# PWR_PMIC.net
KiCad netlist of a schematic drawn in Altium Designer
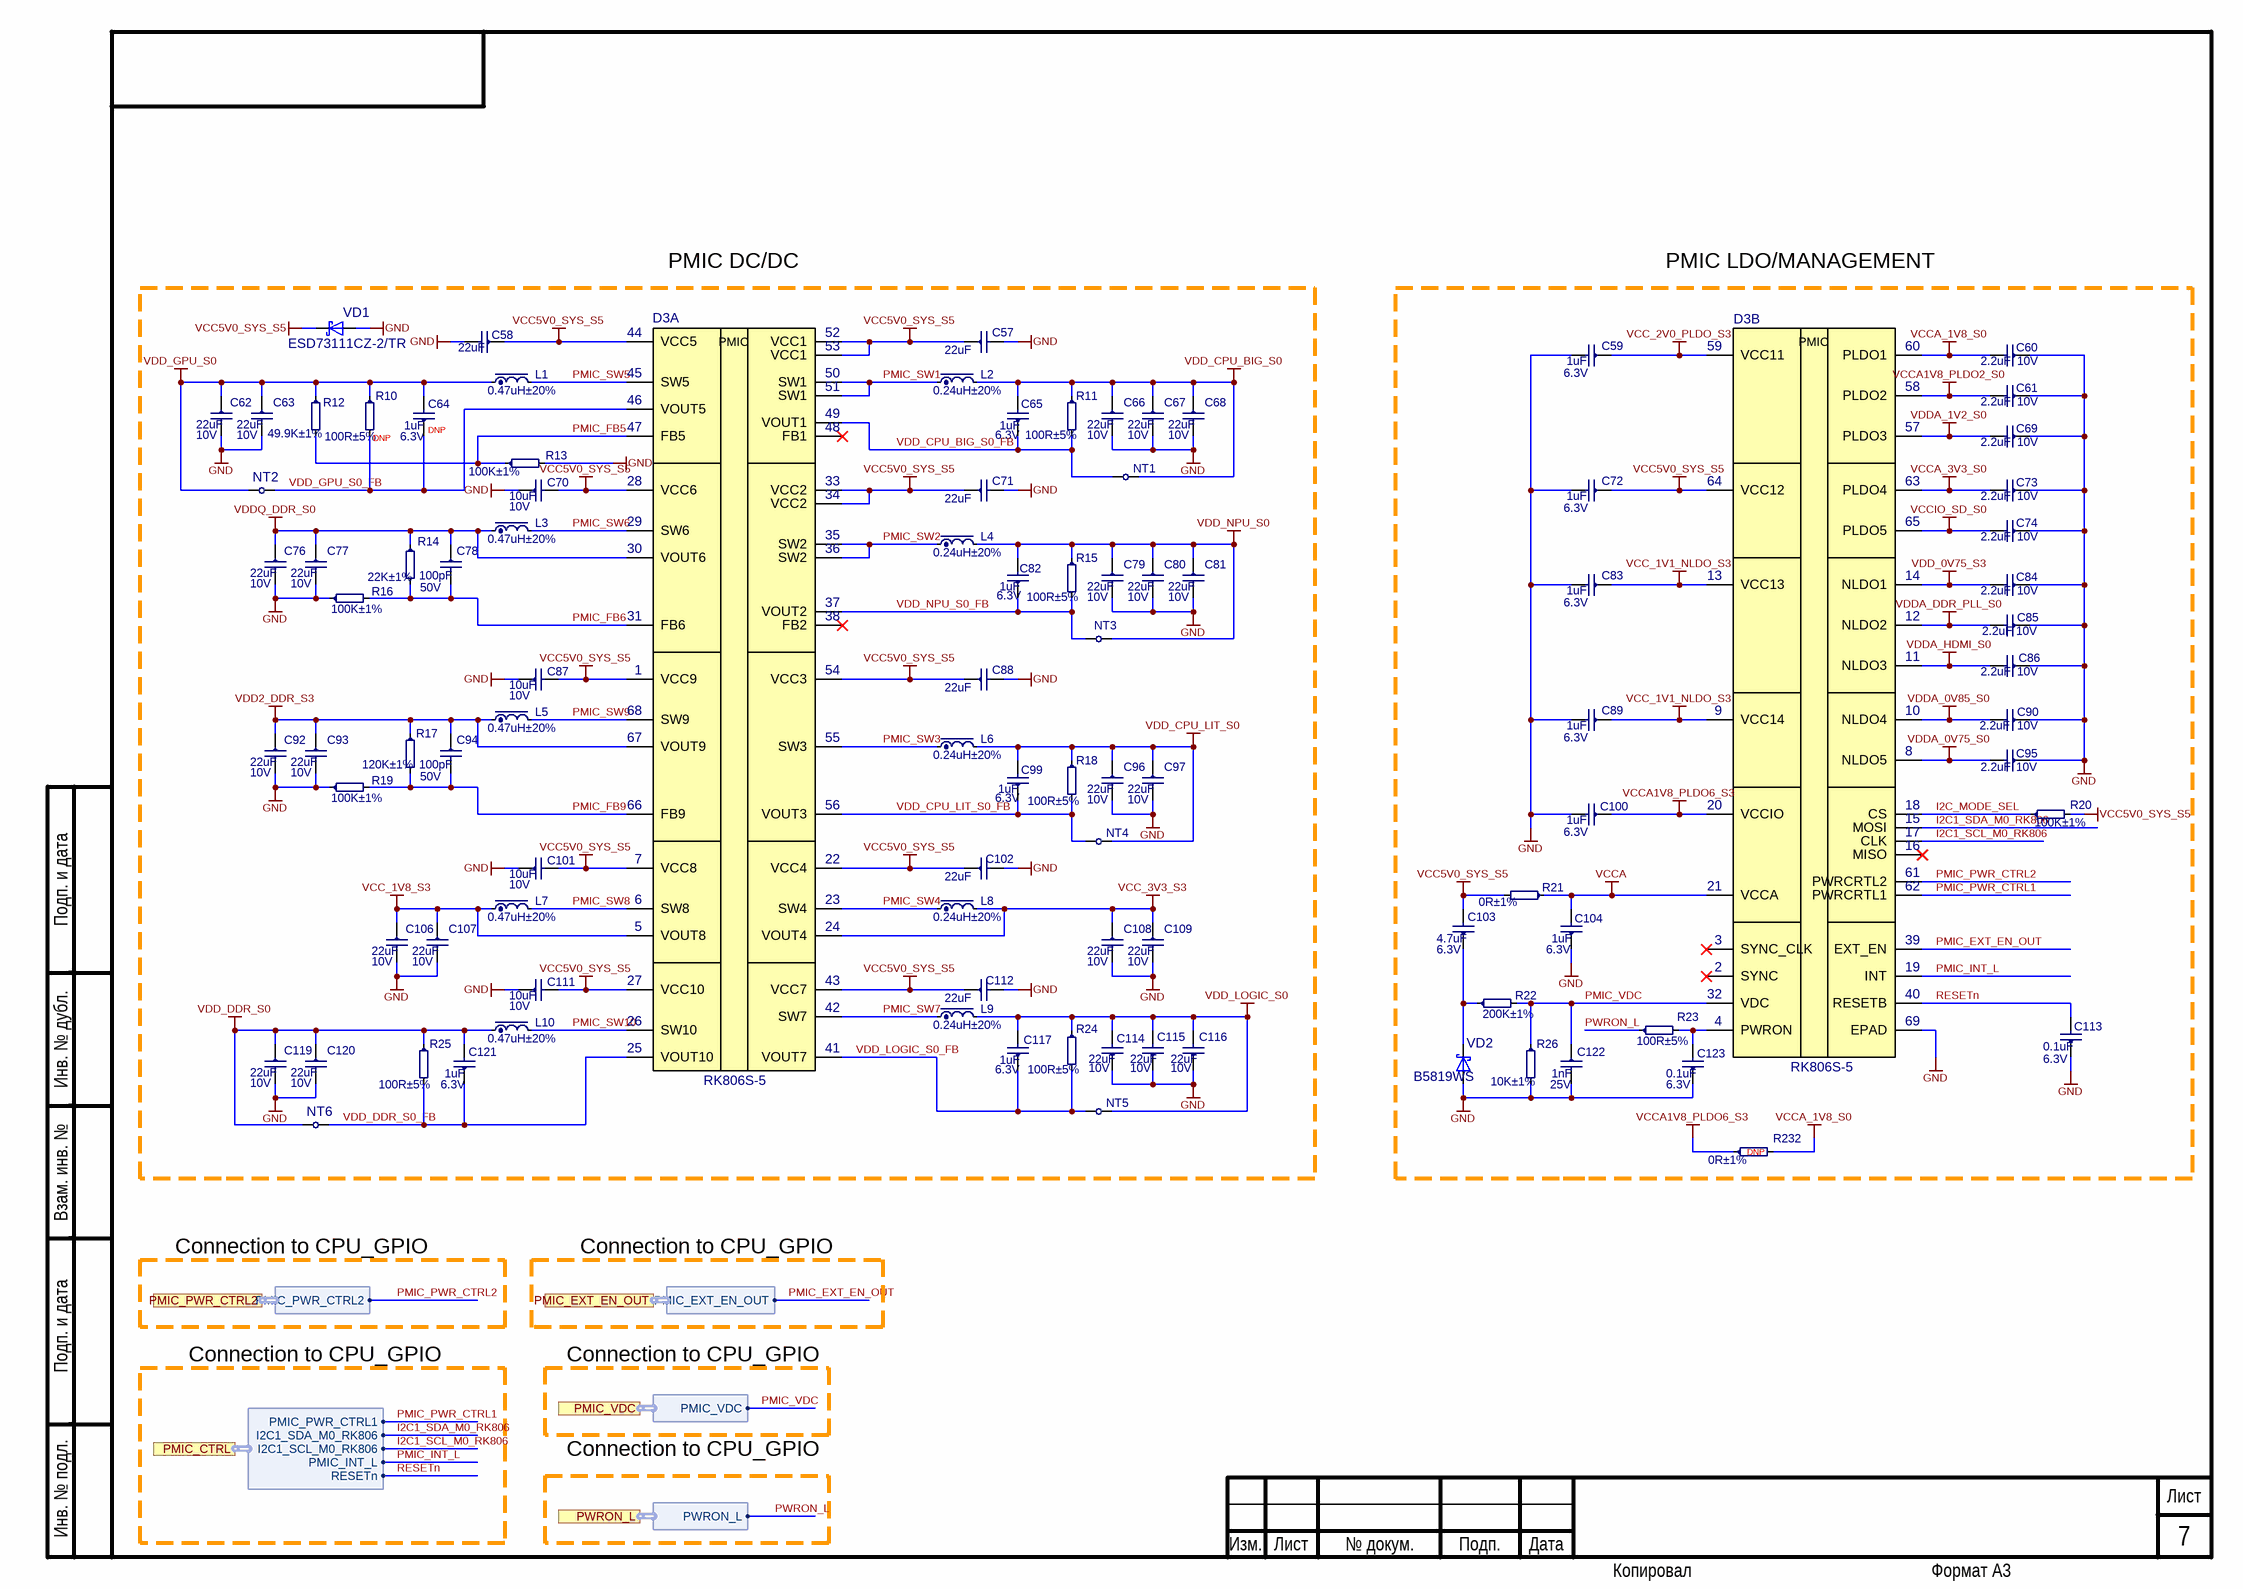
[diagram p0: PWR_PMIC.SchDoc]

(export (version "E")
  (design (tool "Eeschema 10.0.6"))
  (components
    (comp (ref "C57")
      (value "22uF")
      (footprint "C0603")
      (fields
        (field (name "VOLTAGE") "10V")
        (field (name "PART NUMBER") "0603-X5R-10V-22uF±20%")
        (field (name "TOLERANCE") "20%")
      )
      (libsource (lib "ATB") (part "C"))
    )
    (comp (ref "C58")
      (value "22uF")
      (footprint "C0603")
      (fields
        (field (name "VOLTAGE") "10V")
        (field (name "PART NUMBER") "0603-X5R-10V-22uF±20%")
        (field (name "TOLERANCE") "20%")
      )
      (libsource (lib "ATB") (part "C"))
    )
    (comp (ref "C59")
      (value "1uF")
      (footprint "C0201")
      (fields
        (field (name "VOLTAGE") "6.3V")
        (field (name "PART NUMBER") "0201-X5R-6.3V-1uF±20%")
        (field (name "TOLERANCE") "20%")
        (field (name "MANUFACTURER") "Murata Electronics")
      )
      (libsource (lib "ATB") (part "C"))
    )
    (comp (ref "C60")
      (value "2.2uF")
      (footprint "C0402")
      (fields
        (field (name "VOLTAGE") "10V")
        (field (name "PART NUMBER") "0402-X5R-10V-2.2uF±10%")
        (field (name "TOLERANCE") "10%")
        (field (name "MANUFACTURER") "Yageo")
      )
      (libsource (lib "ATB") (part "C"))
    )
    (comp (ref "C61")
      (value "2.2uF")
      (footprint "C0402")
      (fields
        (field (name "VOLTAGE") "10V")
        (field (name "PART NUMBER") "0402-X5R-10V-2.2uF±10%")
        (field (name "TOLERANCE") "10%")
        (field (name "MANUFACTURER") "Yageo")
      )
      (libsource (lib "ATB") (part "C"))
    )
    (comp (ref "C62")
      (value "22uF")
      (footprint "C0603")
      (fields
        (field (name "VOLTAGE") "10V")
        (field (name "PART NUMBER") "0603-X5R-10V-22uF±20%")
        (field (name "TOLERANCE") "20%")
        (field (name "MANUFACTURER") "Samsung Electro-Mechanics")
      )
      (libsource (lib "ATB") (part "C"))
    )
    (comp (ref "C63")
      (value "22uF")
      (footprint "C0603")
      (fields
        (field (name "VOLTAGE") "10V")
        (field (name "PART NUMBER") "0603-X5R-10V-22uF±20%")
        (field (name "TOLERANCE") "20%")
        (field (name "MANUFACTURER") "Samsung Electro-Mechanics")
      )
      (libsource (lib "ATB") (part "C"))
    )
    (comp (ref "C64")
      (value "1uF")
      (footprint "C0201")
      (fields
        (field (name "VOLTAGE") "6.3V")
        (field (name "PART NUMBER") "0201-X5R-6.3V-1uF±20%")
        (field (name "TOLERANCE") "20%")
        (field (name "MANUFACTURER") "Murata Electronics")
      )
      (libsource (lib "ATB") (part "C"))
    )
    (comp (ref "C65")
      (value "1uF")
      (footprint "C0201")
      (fields
        (field (name "VOLTAGE") "6.3V")
        (field (name "PART NUMBER") "0201-X5R-6.3V-1uF±20%")
        (field (name "TOLERANCE") "20%")
        (field (name "MANUFACTURER") "Murata Electronics")
      )
      (libsource (lib "ATB") (part "C"))
    )
    (comp (ref "C66")
      (value "22uF")
      (footprint "C0603")
      (fields
        (field (name "VOLTAGE") "10V")
        (field (name "PART NUMBER") "0603-X5R-10V-22uF±20%")
        (field (name "TOLERANCE") "20%")
        (field (name "MANUFACTURER") "Samsung Electro-Mechanics")
      )
      (libsource (lib "ATB") (part "C"))
    )
    (comp (ref "C67")
      (value "22uF")
      (footprint "C0603")
      (fields
        (field (name "VOLTAGE") "10V")
        (field (name "PART NUMBER") "0603-X5R-10V-22uF±20%")
        (field (name "TOLERANCE") "20%")
        (field (name "MANUFACTURER") "Samsung Electro-Mechanics")
      )
      (libsource (lib "ATB") (part "C"))
    )
    (comp (ref "C68")
      (value "22uF")
      (footprint "C0603")
      (fields
        (field (name "VOLTAGE") "10V")
        (field (name "PART NUMBER") "0603-X5R-10V-22uF±20%")
        (field (name "TOLERANCE") "20%")
        (field (name "MANUFACTURER") "Samsung Electro-Mechanics")
      )
      (libsource (lib "ATB") (part "C"))
    )
    (comp (ref "C69")
      (value "2.2uF")
      (footprint "C0402")
      (fields
        (field (name "VOLTAGE") "10V")
        (field (name "PART NUMBER") "0402-X5R-10V-2.2uF±10%")
        (field (name "TOLERANCE") "10%")
        (field (name "MANUFACTURER") "Yageo")
      )
      (libsource (lib "ATB") (part "C"))
    )
    (comp (ref "C70")
      (value "10uF")
      (footprint "C0603")
      (fields
        (field (name "VOLTAGE") "10V")
        (field (name "PART NUMBER") "0603-X5R-10V-10uF±10%")
        (field (name "TOLERANCE") "10%")
        (field (name "MANUFACTURER") "Yageo")
      )
      (libsource (lib "ATB") (part "C"))
    )
    (comp (ref "C71")
      (value "22uF")
      (footprint "C0603")
      (fields
        (field (name "VOLTAGE") "10V")
        (field (name "PART NUMBER") "0603-X5R-10V-22uF±20%")
        (field (name "TOLERANCE") "20%")
      )
      (libsource (lib "ATB") (part "C"))
    )
    (comp (ref "C72")
      (value "1uF")
      (footprint "C0201")
      (fields
        (field (name "VOLTAGE") "6.3V")
        (field (name "PART NUMBER") "0201-X5R-6.3V-1uF±20%")
        (field (name "TOLERANCE") "20%")
        (field (name "MANUFACTURER") "Murata Electronics")
      )
      (libsource (lib "ATB") (part "C"))
    )
    (comp (ref "C73")
      (value "2.2uF")
      (footprint "C0402")
      (fields
        (field (name "VOLTAGE") "10V")
        (field (name "PART NUMBER") "0402-X5R-10V-2.2uF±10%")
        (field (name "TOLERANCE") "10%")
        (field (name "MANUFACTURER") "Yageo")
      )
      (libsource (lib "ATB") (part "C"))
    )
    (comp (ref "C74")
      (value "2.2uF")
      (footprint "C0402")
      (fields
        (field (name "VOLTAGE") "10V")
        (field (name "PART NUMBER") "0402-X5R-10V-2.2uF±10%")
        (field (name "TOLERANCE") "10%")
        (field (name "MANUFACTURER") "Yageo")
      )
      (libsource (lib "ATB") (part "C"))
    )
    (comp (ref "C76")
      (value "22uF")
      (footprint "C0603")
      (fields
        (field (name "VOLTAGE") "10V")
        (field (name "PART NUMBER") "0603-X5R-10V-22uF±20%")
        (field (name "TOLERANCE") "20%")
        (field (name "MANUFACTURER") "Samsung Electro-Mechanics")
      )
      (libsource (lib "ATB") (part "C"))
    )
    (comp (ref "C77")
      (value "22uF")
      (footprint "C0603")
      (fields
        (field (name "VOLTAGE") "10V")
        (field (name "PART NUMBER") "0603-X5R-10V-22uF±20%")
        (field (name "TOLERANCE") "20%")
        (field (name "MANUFACTURER") "Samsung Electro-Mechanics")
      )
      (libsource (lib "ATB") (part "C"))
    )
    (comp (ref "C78")
      (value "100pF")
      (footprint "C0402")
      (fields
        (field (name "VOLTAGE") "50V")
        (field (name "PART NUMBER") "0402-NP0-50V-100pF±1%")
        (field (name "TOLERANCE") "1%")
        (field (name "MANUFACTURER") "Yageo")
      )
      (libsource (lib "ATB") (part "C"))
    )
    (comp (ref "C79")
      (value "22uF")
      (footprint "C0603")
      (fields
        (field (name "VOLTAGE") "10V")
        (field (name "PART NUMBER") "0603-X5R-10V-22uF±20%")
        (field (name "TOLERANCE") "20%")
        (field (name "MANUFACTURER") "Samsung Electro-Mechanics")
      )
      (libsource (lib "ATB") (part "C"))
    )
    (comp (ref "C80")
      (value "22uF")
      (footprint "C0603")
      (fields
        (field (name "VOLTAGE") "10V")
        (field (name "PART NUMBER") "0603-X5R-10V-22uF±20%")
        (field (name "TOLERANCE") "20%")
        (field (name "MANUFACTURER") "Samsung Electro-Mechanics")
      )
      (libsource (lib "ATB") (part "C"))
    )
    (comp (ref "C81")
      (value "22uF")
      (footprint "C0603")
      (fields
        (field (name "VOLTAGE") "10V")
        (field (name "PART NUMBER") "0603-X5R-10V-22uF±20%")
        (field (name "TOLERANCE") "20%")
        (field (name "MANUFACTURER") "Samsung Electro-Mechanics")
      )
      (libsource (lib "ATB") (part "C"))
    )
    (comp (ref "C82")
      (value "1uF")
      (footprint "C0201")
      (fields
        (field (name "VOLTAGE") "6.3V")
        (field (name "PART NUMBER") "0201-X5R-6.3V-1uF±20%")
        (field (name "TOLERANCE") "20%")
        (field (name "MANUFACTURER") "Murata Electronics")
      )
      (libsource (lib "ATB") (part "C"))
    )
    (comp (ref "C83")
      (value "1uF")
      (footprint "C0201")
      (fields
        (field (name "VOLTAGE") "6.3V")
        (field (name "PART NUMBER") "0201-X5R-6.3V-1uF±20%")
        (field (name "TOLERANCE") "20%")
        (field (name "MANUFACTURER") "Murata Electronics")
      )
      (libsource (lib "ATB") (part "C"))
    )
    (comp (ref "C84")
      (value "2.2uF")
      (footprint "C0402")
      (fields
        (field (name "VOLTAGE") "10V")
        (field (name "PART NUMBER") "0402-X5R-10V-2.2uF±10%")
        (field (name "TOLERANCE") "10%")
        (field (name "MANUFACTURER") "Yageo")
      )
      (libsource (lib "ATB") (part "C"))
    )
    (comp (ref "C85")
      (value "2.2uF")
      (footprint "C0402")
      (fields
        (field (name "VOLTAGE") "10V")
        (field (name "PART NUMBER") "0402-X5R-10V-2.2uF±10%")
        (field (name "TOLERANCE") "10%")
        (field (name "MANUFACTURER") "Yageo")
      )
      (libsource (lib "ATB") (part "C"))
    )
    (comp (ref "C86")
      (value "2.2uF")
      (footprint "C0402")
      (fields
        (field (name "VOLTAGE") "10V")
        (field (name "PART NUMBER") "0402-X5R-10V-2.2uF±10%")
        (field (name "TOLERANCE") "10%")
        (field (name "MANUFACTURER") "Yageo")
      )
      (libsource (lib "ATB") (part "C"))
    )
    (comp (ref "C87")
      (value "10uF")
      (footprint "C0603")
      (fields
        (field (name "VOLTAGE") "10V")
        (field (name "PART NUMBER") "0603-X5R-10V-10uF±10%")
        (field (name "TOLERANCE") "10%")
        (field (name "MANUFACTURER") "Yageo")
      )
      (libsource (lib "ATB") (part "C"))
    )
    (comp (ref "C88")
      (value "22uF")
      (footprint "C0603")
      (fields
        (field (name "VOLTAGE") "10V")
        (field (name "PART NUMBER") "0603-X5R-10V-22uF±20%")
        (field (name "TOLERANCE") "20%")
      )
      (libsource (lib "ATB") (part "C"))
    )
    (comp (ref "C89")
      (value "1uF")
      (footprint "C0201")
      (fields
        (field (name "VOLTAGE") "6.3V")
        (field (name "PART NUMBER") "0201-X5R-6.3V-1uF±20%")
        (field (name "TOLERANCE") "20%")
        (field (name "MANUFACTURER") "Murata Electronics")
      )
      (libsource (lib "ATB") (part "C"))
    )
    (comp (ref "C90")
      (value "2.2uF")
      (footprint "C0402")
      (fields
        (field (name "VOLTAGE") "10V")
        (field (name "PART NUMBER") "0402-X5R-10V-2.2uF±10%")
        (field (name "TOLERANCE") "10%")
        (field (name "MANUFACTURER") "Yageo")
      )
      (libsource (lib "ATB") (part "C"))
    )
    (comp (ref "C92")
      (value "22uF")
      (footprint "C0603")
      (fields
        (field (name "VOLTAGE") "10V")
        (field (name "PART NUMBER") "0603-X5R-10V-22uF±20%")
        (field (name "TOLERANCE") "20%")
        (field (name "MANUFACTURER") "Samsung Electro-Mechanics")
      )
      (libsource (lib "ATB") (part "C"))
    )
    (comp (ref "C93")
      (value "22uF")
      (footprint "C0603")
      (fields
        (field (name "VOLTAGE") "10V")
        (field (name "PART NUMBER") "0603-X5R-10V-22uF±20%")
        (field (name "TOLERANCE") "20%")
        (field (name "MANUFACTURER") "Samsung Electro-Mechanics")
      )
      (libsource (lib "ATB") (part "C"))
    )
    (comp (ref "C94")
      (value "100pF")
      (footprint "C0402")
      (fields
        (field (name "VOLTAGE") "50V")
        (field (name "PART NUMBER") "0402-NP0-50V-100pF±1%")
        (field (name "TOLERANCE") "1%")
        (field (name "MANUFACTURER") "Yageo")
      )
      (libsource (lib "ATB") (part "C"))
    )
    (comp (ref "C95")
      (value "2.2uF")
      (footprint "C0402")
      (fields
        (field (name "VOLTAGE") "10V")
        (field (name "PART NUMBER") "0402-X5R-10V-2.2uF±10%")
        (field (name "TOLERANCE") "10%")
        (field (name "MANUFACTURER") "Yageo")
      )
      (libsource (lib "ATB") (part "C"))
    )
    (comp (ref "C96")
      (value "22uF")
      (footprint "C0603")
      (fields
        (field (name "VOLTAGE") "10V")
        (field (name "PART NUMBER") "0603-X5R-10V-22uF±20%")
        (field (name "TOLERANCE") "20%")
        (field (name "MANUFACTURER") "Samsung Electro-Mechanics")
      )
      (libsource (lib "ATB") (part "C"))
    )
    (comp (ref "C97")
      (value "22uF")
      (footprint "C0603")
      (fields
        (field (name "VOLTAGE") "10V")
        (field (name "PART NUMBER") "0603-X5R-10V-22uF±20%")
        (field (name "TOLERANCE") "20%")
        (field (name "MANUFACTURER") "Samsung Electro-Mechanics")
      )
      (libsource (lib "ATB") (part "C"))
    )
    (comp (ref "C99")
      (value "1uF")
      (footprint "C0201")
      (fields
        (field (name "VOLTAGE") "6.3V")
        (field (name "PART NUMBER") "0201-X5R-6.3V-1uF±20%")
        (field (name "TOLERANCE") "20%")
        (field (name "MANUFACTURER") "Murata Electronics")
      )
      (libsource (lib "ATB") (part "C"))
    )
    (comp (ref "C100")
      (value "1uF")
      (footprint "C0201")
      (fields
        (field (name "VOLTAGE") "6.3V")
        (field (name "PART NUMBER") "0201-X5R-6.3V-1uF±20%")
        (field (name "TOLERANCE") "20%")
        (field (name "MANUFACTURER") "Murata Electronics")
      )
      (libsource (lib "ATB") (part "C"))
    )
    (comp (ref "C101")
      (value "10uF")
      (footprint "C0603")
      (fields
        (field (name "VOLTAGE") "10V")
        (field (name "PART NUMBER") "0603-X5R-10V-10uF±10%")
        (field (name "TOLERANCE") "10%")
        (field (name "MANUFACTURER") "Yageo")
      )
      (libsource (lib "ATB") (part "C"))
    )
    (comp (ref "C102")
      (value "22uF")
      (footprint "C0603")
      (fields
        (field (name "VOLTAGE") "10V")
        (field (name "PART NUMBER") "0603-X5R-10V-22uF±20%")
        (field (name "TOLERANCE") "20%")
      )
      (libsource (lib "ATB") (part "C"))
    )
    (comp (ref "C103")
      (value "4.7uF")
      (footprint "C0201")
      (fields
        (field (name "VOLTAGE") "6.3V")
        (field (name "PART NUMBER") "0201-X5R-6.3V-4.7uF±20%")
        (field (name "TOLERANCE") "20%")
        (field (name "MANUFACTURER") "Murata Electronics")
      )
      (libsource (lib "ATB") (part "C"))
    )
    (comp (ref "C104")
      (value "1uF")
      (footprint "C0201")
      (fields
        (field (name "VOLTAGE") "6.3V")
        (field (name "PART NUMBER") "0201-X5R-6.3V-1uF±20%")
        (field (name "TOLERANCE") "20%")
        (field (name "MANUFACTURER") "Murata Electronics")
      )
      (libsource (lib "ATB") (part "C"))
    )
    (comp (ref "C106")
      (value "22uF")
      (footprint "C0603")
      (fields
        (field (name "VOLTAGE") "10V")
        (field (name "PART NUMBER") "0603-X5R-10V-22uF±20%")
        (field (name "TOLERANCE") "20%")
        (field (name "MANUFACTURER") "Samsung Electro-Mechanics")
      )
      (libsource (lib "ATB") (part "C"))
    )
    (comp (ref "C107")
      (value "22uF")
      (footprint "C0603")
      (fields
        (field (name "VOLTAGE") "10V")
        (field (name "PART NUMBER") "0603-X5R-10V-22uF±20%")
        (field (name "TOLERANCE") "20%")
        (field (name "MANUFACTURER") "Samsung Electro-Mechanics")
      )
      (libsource (lib "ATB") (part "C"))
    )
    (comp (ref "C108")
      (value "22uF")
      (footprint "C0603")
      (fields
        (field (name "VOLTAGE") "10V")
        (field (name "PART NUMBER") "0603-X5R-10V-22uF±20%")
        (field (name "TOLERANCE") "20%")
        (field (name "MANUFACTURER") "Samsung Electro-Mechanics")
      )
      (libsource (lib "ATB") (part "C"))
    )
    (comp (ref "C109")
      (value "22uF")
      (footprint "C0603")
      (fields
        (field (name "VOLTAGE") "10V")
        (field (name "PART NUMBER") "0603-X5R-10V-22uF±20%")
        (field (name "TOLERANCE") "20%")
        (field (name "MANUFACTURER") "Samsung Electro-Mechanics")
      )
      (libsource (lib "ATB") (part "C"))
    )
    (comp (ref "C111")
      (value "10uF")
      (footprint "C0603")
      (fields
        (field (name "VOLTAGE") "10V")
        (field (name "PART NUMBER") "0603-X5R-10V-10uF±10%")
        (field (name "TOLERANCE") "10%")
        (field (name "MANUFACTURER") "Yageo")
      )
      (libsource (lib "ATB") (part "C"))
    )
    (comp (ref "C112")
      (value "22uF")
      (footprint "C0603")
      (fields
        (field (name "VOLTAGE") "10V")
        (field (name "PART NUMBER") "0603-X5R-10V-22uF±20%")
        (field (name "TOLERANCE") "20%")
      )
      (libsource (lib "ATB") (part "C"))
    )
    (comp (ref "C113")
      (value "0.1uF")
      (footprint "C0201")
      (fields
        (field (name "VOLTAGE") "6.3V")
        (field (name "PART NUMBER") "0201-X5R-6.3V-0.1uF±10%")
        (field (name "TOLERANCE") "10%")
        (field (name "MANUFACTURER") "Yageo")
      )
      (libsource (lib "ATB") (part "C"))
    )
    (comp (ref "C114")
      (value "22uF")
      (footprint "C0603")
      (fields
        (field (name "VOLTAGE") "10V")
        (field (name "PART NUMBER") "0603-X5R-10V-22uF±20%")
        (field (name "TOLERANCE") "20%")
        (field (name "MANUFACTURER") "Samsung Electro-Mechanics")
      )
      (libsource (lib "ATB") (part "C"))
    )
    (comp (ref "C115")
      (value "22uF")
      (footprint "C0603")
      (fields
        (field (name "VOLTAGE") "10V")
        (field (name "PART NUMBER") "0603-X5R-10V-22uF±20%")
        (field (name "TOLERANCE") "20%")
        (field (name "MANUFACTURER") "Samsung Electro-Mechanics")
      )
      (libsource (lib "ATB") (part "C"))
    )
    (comp (ref "C116")
      (value "22uF")
      (footprint "C0603")
      (fields
        (field (name "VOLTAGE") "10V")
        (field (name "PART NUMBER") "0603-X5R-10V-22uF±20%")
        (field (name "TOLERANCE") "20%")
        (field (name "MANUFACTURER") "Samsung Electro-Mechanics")
      )
      (libsource (lib "ATB") (part "C"))
    )
    (comp (ref "C117")
      (value "1uF")
      (footprint "C0201")
      (fields
        (field (name "VOLTAGE") "6.3V")
        (field (name "PART NUMBER") "0201-X5R-6.3V-1uF±20%")
        (field (name "TOLERANCE") "20%")
        (field (name "MANUFACTURER") "Murata Electronics")
      )
      (libsource (lib "ATB") (part "C"))
    )
    (comp (ref "C119")
      (value "22uF")
      (footprint "C0603")
      (fields
        (field (name "VOLTAGE") "10V")
        (field (name "PART NUMBER") "0603-X5R-10V-22uF±20%")
        (field (name "TOLERANCE") "20%")
        (field (name "MANUFACTURER") "Samsung Electro-Mechanics")
      )
      (libsource (lib "ATB") (part "C"))
    )
    (comp (ref "C120")
      (value "22uF")
      (footprint "C0603")
      (fields
        (field (name "VOLTAGE") "10V")
        (field (name "PART NUMBER") "0603-X5R-10V-22uF±20%")
        (field (name "TOLERANCE") "20%")
        (field (name "MANUFACTURER") "Samsung Electro-Mechanics")
      )
      (libsource (lib "ATB") (part "C"))
    )
    (comp (ref "C121")
      (value "1uF")
      (footprint "C0201")
      (fields
        (field (name "VOLTAGE") "6.3V")
        (field (name "PART NUMBER") "0201-X5R-6.3V-1uF±20%")
        (field (name "TOLERANCE") "20%")
        (field (name "MANUFACTURER") "Murata Electronics")
      )
      (libsource (lib "ATB") (part "C"))
    )
    (comp (ref "C122")
      (value "1nF")
      (footprint "C0201")
      (fields
        (field (name "VOLTAGE") "25V")
        (field (name "PART NUMBER") "0201-C0G-25V-1nF±5%")
        (field (name "TOLERANCE") "5%")
        (field (name "MANUFACTURER") "muRata")
      )
      (libsource (lib "ATB") (part "C"))
    )
    (comp (ref "C123")
      (value "0.1uF")
      (footprint "C0201")
      (fields
        (field (name "VOLTAGE") "6.3V")
        (field (name "PART NUMBER") "0201-X5R-6.3V-0.1uF±10%")
        (field (name "TOLERANCE") "10%")
        (field (name "MANUFACTURER") "Yageo")
      )
      (libsource (lib "ATB") (part "C"))
    )
    (comp (ref "D3")
      (value "RK806S-5")
      (footprint "RK806-1")
      (description "Power Management")
      (fields (field (name "MANUFACTURER") "Rockchip"))
      (libsource (lib "LIB_RK") (part "RK806S-5"))
    )
    (comp (ref "L1")
      (value "0.47uH±20%")
      (footprint "L0806")
      (fields
        (field (name "PART NUMBER") "0806-5A-0.47uH±20%")
        (field (name "TOLERANCE") "20%")
        (field (name "MANUFACTURER") "INPAQ")
      )
      (libsource (lib "ATB") (part "L"))
    )
    (comp (ref "L2")
      (value "0.24uH±20%")
      (footprint "L0806")
      (fields
        (field (name "PART NUMBER") "0806-4.4A-0.24uH±20%")
        (field (name "TOLERANCE") "20%")
        (field (name "MANUFACTURER") "cjiang")
      )
      (libsource (lib "ATB") (part "L"))
    )
    (comp (ref "L3")
      (value "0.47uH±20%")
      (footprint "L0806")
      (fields
        (field (name "PART NUMBER") "0806-5A-0.47uH±20%")
        (field (name "TOLERANCE") "20%")
        (field (name "MANUFACTURER") "INPAQ")
      )
      (libsource (lib "ATB") (part "L"))
    )
    (comp (ref "L4")
      (value "0.24uH±20%")
      (footprint "L0806")
      (fields
        (field (name "PART NUMBER") "0806-4.4A-0.24uH±20%")
        (field (name "TOLERANCE") "20%")
        (field (name "MANUFACTURER") "cjiang")
      )
      (libsource (lib "ATB") (part "L"))
    )
    (comp (ref "L5")
      (value "0.47uH±20%")
      (footprint "L0806")
      (fields
        (field (name "PART NUMBER") "0806-5A-0.47uH±20%")
        (field (name "TOLERANCE") "20%")
        (field (name "MANUFACTURER") "INPAQ")
      )
      (libsource (lib "ATB") (part "L"))
    )
    (comp (ref "L6")
      (value "0.24uH±20%")
      (footprint "L0806")
      (fields
        (field (name "PART NUMBER") "0806-4.4A-0.24uH±20%")
        (field (name "TOLERANCE") "20%")
        (field (name "MANUFACTURER") "cjiang")
      )
      (libsource (lib "ATB") (part "L"))
    )
    (comp (ref "L7")
      (value "0.47uH±20%")
      (footprint "L0806")
      (fields
        (field (name "PART NUMBER") "0806-5A-0.47uH±20%")
        (field (name "TOLERANCE") "20%")
        (field (name "MANUFACTURER") "INPAQ")
      )
      (libsource (lib "ATB") (part "L"))
    )
    (comp (ref "L8")
      (value "0.24uH±20%")
      (footprint "L0806")
      (fields
        (field (name "PART NUMBER") "0806-4.4A-0.24uH±20%")
        (field (name "TOLERANCE") "20%")
        (field (name "MANUFACTURER") "cjiang")
      )
      (libsource (lib "ATB") (part "L"))
    )
    (comp (ref "L9")
      (value "0.24uH±20%")
      (footprint "L0806")
      (fields
        (field (name "PART NUMBER") "0806-4.4A-0.24uH±20%")
        (field (name "TOLERANCE") "20%")
        (field (name "MANUFACTURER") "cjiang")
      )
      (libsource (lib "ATB") (part "L"))
    )
    (comp (ref "L10")
      (value "0.47uH±20%")
      (footprint "L0806")
      (fields
        (field (name "PART NUMBER") "0806-5A-0.47uH±20%")
        (field (name "TOLERANCE") "20%")
        (field (name "MANUFACTURER") "INPAQ")
      )
      (libsource (lib "ATB") (part "L"))
    )
    (comp (ref "NT1")
      (value "~")
      (footprint "NetTie_0.6mm_close")
      (fields (field (name "PART NUMBER") "Перемычка закрытая_0.6мм"))
      (libsource (lib "ATB") (part "NetTie"))
    )
    (comp (ref "NT2")
      (value "~")
      (footprint "NetTie_0.6mm_close")
      (fields (field (name "PART NUMBER") "Перемычка закрытая_0.6мм"))
      (libsource (lib "ATB") (part "NetTie"))
    )
    (comp (ref "NT3")
      (value "~")
      (footprint "NetTie_0.6mm_close")
      (fields (field (name "PART NUMBER") "Перемычка закрытая_0.6мм"))
      (libsource (lib "ATB") (part "NetTie"))
    )
    (comp (ref "NT4")
      (value "~")
      (footprint "NetTie_0.6mm_close")
      (fields (field (name "PART NUMBER") "Перемычка закрытая_0.6мм"))
      (libsource (lib "ATB") (part "NetTie"))
    )
    (comp (ref "NT5")
      (value "~")
      (footprint "NetTie_0.6mm_close")
      (fields (field (name "PART NUMBER") "Перемычка закрытая_0.6мм"))
      (libsource (lib "ATB") (part "NetTie"))
    )
    (comp (ref "NT6")
      (value "~")
      (footprint "NetTie_0.6mm_close")
      (fields (field (name "PART NUMBER") "Перемычка закрытая_0.6мм"))
      (libsource (lib "ATB") (part "NetTie"))
    )
    (comp (ref "R10")
      (value "100R±5%")
      (footprint "R0201")
      (fields
        (field (name "PART NUMBER") "0201-0.05W-100R-200ppm-5%")
        (field (name "TOLERANCE") "5%")
        (field (name "MANUFACTURER") "Yageo")
      )
      (libsource (lib "ATB") (part "R"))
    )
    (comp (ref "R11")
      (value "100R±5%")
      (footprint "R0201")
      (fields
        (field (name "PART NUMBER") "0201-0.05W-100R-200ppm-5%")
        (field (name "TOLERANCE") "5%")
        (field (name "MANUFACTURER") "Yageo")
      )
      (libsource (lib "ATB") (part "R"))
    )
    (comp (ref "R12")
      (value "49.9K±1%")
      (footprint "R0402")
      (description "Chip Resistor 0402 49.9kΩ ±1% 50V ±100ppm/℃ Thick Film")
      (fields (field (name "PART NUMBER") "0402-0.0625W-49.9K-100ppm±1%") (field (name "TOLERANCE") "1%"))
      (libsource (lib "ATB") (part "R"))
    )
    (comp (ref "R13")
      (value "100K±1%")
      (footprint "R0402")
      (description "Chip Resistor 0402 100kΩ ±1% 50V ±100ppm/℃ Thick Film")
      (fields (field (name "PART NUMBER") "0402-0.0625W-100K-100ppm±1%") (field (name "TOLERANCE") "1%"))
      (libsource (lib "ATB") (part "R"))
    )
    (comp (ref "R14")
      (value "22K±1%")
      (footprint "R0402")
      (fields
        (field (name "PART NUMBER") "0402-0.0625W-22K-100ppm±1%")
        (field (name "TOLERANCE") "1%")
        (field (name "MANUFACTURER") "Yageo")
      )
      (libsource (lib "ATB") (part "R"))
    )
    (comp (ref "R15")
      (value "100R±5%")
      (footprint "R0201")
      (fields
        (field (name "PART NUMBER") "0201-0.05W-100R-200ppm-5%")
        (field (name "TOLERANCE") "5%")
        (field (name "MANUFACTURER") "Yageo")
      )
      (libsource (lib "ATB") (part "R"))
    )
    (comp (ref "R16")
      (value "100K±1%")
      (footprint "R0402")
      (description "Chip Resistor 0402 100kΩ ±1% 50V ±100ppm/℃ Thick Film")
      (fields (field (name "PART NUMBER") "0402-0.0625W-100K-100ppm±1%") (field (name "TOLERANCE") "1%"))
      (libsource (lib "ATB") (part "R"))
    )
    (comp (ref "R17")
      (value "120K±1%")
      (footprint "R0402")
      (fields
        (field (name "PART NUMBER") "0402-0.0625W-120K-100ppm±1%")
        (field (name "TOLERANCE") "1%")
        (field (name "MANUFACTURER") "Yageo")
      )
      (libsource (lib "ATB") (part "R"))
    )
    (comp (ref "R18")
      (value "100R±5%")
      (footprint "R0201")
      (fields
        (field (name "PART NUMBER") "0201-0.05W-100R-200ppm-5%")
        (field (name "TOLERANCE") "5%")
        (field (name "MANUFACTURER") "Yageo")
      )
      (libsource (lib "ATB") (part "R"))
    )
    (comp (ref "R19")
      (value "100K±1%")
      (footprint "R0402")
      (description "Chip Resistor 0402 100kΩ ±1% 50V ±100ppm/℃ Thick Film")
      (fields (field (name "PART NUMBER") "0402-0.0625W-100K-100ppm±1%") (field (name "TOLERANCE") "1%"))
      (libsource (lib "ATB") (part "R"))
    )
    (comp (ref "R20")
      (value "100K±1%")
      (footprint "R0201")
      (fields
        (field (name "PART NUMBER") "0201-0.05W-100K-5%")
        (field (name "TOLERANCE") "1%")
        (field (name "MANUFACTURER") "Yageo")
      )
      (libsource (lib "ATB") (part "R"))
    )
    (comp (ref "R21")
      (value "0R±1%")
      (footprint "R0402")
      (description "Chip Resistor 0402 0Ω ±1% 50V ±100ppm/℃ Thick Film")
      (fields (field (name "PART NUMBER") "0402-0.0625W-0R-100ppm±1%") (field (name "TOLERANCE") "1%"))
      (libsource (lib "ATB") (part "R"))
    )
    (comp (ref "R22")
      (value "200K±1%")
      (footprint "R0201")
      (fields
        (field (name "PART NUMBER") "0201-0.05W-200K-100ppm-1%")
        (field (name "TOLERANCE") "1%")
        (field (name "MANUFACTURER") "Yageo")
      )
      (libsource (lib "ATB") (part "R"))
    )
    (comp (ref "R23")
      (value "100R±5%")
      (footprint "R0201")
      (fields
        (field (name "PART NUMBER") "0201-0.05W-100R-200ppm-5%")
        (field (name "TOLERANCE") "5%")
        (field (name "MANUFACTURER") "Yageo")
      )
      (libsource (lib "ATB") (part "R"))
    )
    (comp (ref "R24")
      (value "100R±5%")
      (footprint "R0201")
      (fields
        (field (name "PART NUMBER") "0201-0.05W-100R-200ppm-5%")
        (field (name "TOLERANCE") "5%")
        (field (name "MANUFACTURER") "Yageo")
      )
      (libsource (lib "ATB") (part "R"))
    )
    (comp (ref "R25")
      (value "100R±5%")
      (footprint "R0201")
      (fields
        (field (name "PART NUMBER") "0201-0.05W-100R-200ppm-5%")
        (field (name "TOLERANCE") "5%")
        (field (name "MANUFACTURER") "Yageo")
      )
      (libsource (lib "ATB") (part "R"))
    )
    (comp (ref "R26")
      (value "10K±1%")
      (footprint "R0201")
      (fields
        (field (name "PART NUMBER") "0201-0.05W-10K-100ppm-1%")
        (field (name "TOLERANCE") "1%")
        (field (name "MANUFACTURER") "Yageo")
      )
      (libsource (lib "ATB") (part "R"))
    )
    (comp (ref "R232")
      (value "0R±1%")
      (footprint "R0402")
      (description "Chip Resistor 0402 0Ω ±1% 50V ±100ppm/℃ Thick Film")
      (fields (field (name "PART NUMBER") "0402-0.0625W-0R-100ppm±1%") (field (name "TOLERANCE") "1%"))
      (libsource (lib "ATB") (part "R"))
    )
    (comp (ref "VD1")
      (value "ESD73111CZ-2/TR")
      (footprint "ESD73111CZ-2/TR")
      (description "6.5VC Clamp 6A@8/20us Ipp ESD DIODE DWN0603-2L")
      (fields (field (name "MANUFACTURER") "WILLSEMI"))
      (libsource (lib "LIB_RK") (part "ESD73111CZ-2/TR"))
    )
    (comp (ref "VD2")
      (value "B5819WS")
      (footprint "B5819WS")
      (description "Rectifier Diode, Schottky, 1 Phase, 1 Element, 1A, 40V V(RRM), Silicon")
      (libsource (lib "LIB_RK") (part "B5819WS"))
    )
  )
  (nets
    (net (code "2") (name "/I2C1_SCL_M0_RK806") (class "Default")
      (node (ref "D3") (pin "17") (pinfunction "CLK_17") (pintype "passive"))
    )
    (net (code "3") (name "/I2C1_SDA_M0_RK806") (class "Default")
      (node (ref "D3") (pin "15") (pinfunction "MOSI_15") (pintype "passive"))
    )
    (net (code "4") (name "/I2C_MODE_SEL") (class "Default")
      (node (ref "D3") (pin "18") (pinfunction "CS_18") (pintype "passive"))
      (node (ref "R20") (pin "1") (pinfunction "1_1") (pintype "passive"))
    )
    (net (code "5") (name "/PMIC_EXT_EN_OUT") (class "Default")
      (node (ref "D3") (pin "39") (pinfunction "EXT_EN_39") (pintype "passive"))
    )
    (net (code "6") (name "/PMIC_FB5") (class "Default")
      (node (ref "D3") (pin "47") (pinfunction "FB5_47") (pintype "passive"))
      (node (ref "R12") (pin "2") (pinfunction "2_2") (pintype "passive"))
      (node (ref "R13") (pin "1") (pinfunction "1_1") (pintype "passive"))
    )
    (net (code "7") (name "/PMIC_FB6") (class "Default")
      (node (ref "C78") (pin "2") (pinfunction "2_2") (pintype "passive"))
      (node (ref "D3") (pin "31") (pinfunction "FB6_31") (pintype "passive"))
      (node (ref "R14") (pin "2") (pinfunction "2_2") (pintype "passive"))
      (node (ref "R16") (pin "2") (pinfunction "2_2") (pintype "passive"))
    )
    (net (code "8") (name "/PMIC_FB9") (class "Default")
      (node (ref "C94") (pin "2") (pinfunction "2_2") (pintype "passive"))
      (node (ref "D3") (pin "66") (pinfunction "FB9_66") (pintype "passive"))
      (node (ref "R17") (pin "2") (pinfunction "2_2") (pintype "passive"))
      (node (ref "R19") (pin "2") (pinfunction "2_2") (pintype "passive"))
    )
    (net (code "9") (name "/PMIC_INT_L") (class "Default")
      (node (ref "D3") (pin "19") (pinfunction "INT_19") (pintype "passive"))
    )
    (net (code "10") (name "/PMIC_PWR_CTRL1") (class "Default")
      (node (ref "D3") (pin "62") (pinfunction "PWRCRTL1_62") (pintype "passive"))
    )
    (net (code "11") (name "/PMIC_PWR_CTRL2") (class "Default")
      (node (ref "D3") (pin "61") (pinfunction "PWRCRTL2_61") (pintype "passive"))
    )
    (net (code "12") (name "/PMIC_SW1") (class "Default")
      (node (ref "D3") (pin "50") (pinfunction "SW1_50") (pintype "passive"))
      (node (ref "D3") (pin "51") (pinfunction "SW1_51") (pintype "passive"))
      (node (ref "L2") (pin "1") (pinfunction "1_1") (pintype "passive"))
    )
    (net (code "13") (name "/PMIC_SW2") (class "Default")
      (node (ref "D3") (pin "35") (pinfunction "SW2_35") (pintype "passive"))
      (node (ref "D3") (pin "36") (pinfunction "SW2_36") (pintype "passive"))
      (node (ref "L4") (pin "1") (pinfunction "1_1") (pintype "passive"))
    )
    (net (code "14") (name "/PMIC_SW3") (class "Default")
      (node (ref "D3") (pin "55") (pinfunction "SW3_55") (pintype "passive"))
      (node (ref "L6") (pin "1") (pinfunction "1_1") (pintype "passive"))
    )
    (net (code "15") (name "/PMIC_SW4") (class "Default")
      (node (ref "D3") (pin "23") (pinfunction "SW4_23") (pintype "passive"))
      (node (ref "L8") (pin "1") (pinfunction "1_1") (pintype "passive"))
    )
    (net (code "16") (name "/PMIC_SW5") (class "Default")
      (node (ref "D3") (pin "45") (pinfunction "SW5_45") (pintype "passive"))
      (node (ref "L1") (pin "2") (pinfunction "2_2") (pintype "passive"))
    )
    (net (code "17") (name "/PMIC_SW6") (class "Default")
      (node (ref "D3") (pin "29") (pinfunction "SW6_29") (pintype "passive"))
      (node (ref "L3") (pin "2") (pinfunction "2_2") (pintype "passive"))
    )
    (net (code "18") (name "/PMIC_SW7") (class "Default")
      (node (ref "D3") (pin "42") (pinfunction "SW7_42") (pintype "passive"))
      (node (ref "L9") (pin "1") (pinfunction "1_1") (pintype "passive"))
    )
    (net (code "19") (name "/PMIC_SW8") (class "Default")
      (node (ref "D3") (pin "6") (pinfunction "SW8_6") (pintype "passive"))
      (node (ref "L7") (pin "2") (pinfunction "2_2") (pintype "passive"))
    )
    (net (code "20") (name "/PMIC_SW9") (class "Default")
      (node (ref "D3") (pin "68") (pinfunction "SW9_68") (pintype "passive"))
      (node (ref "L5") (pin "2") (pinfunction "2_2") (pintype "passive"))
    )
    (net (code "21") (name "/PMIC_SW10") (class "Default")
      (node (ref "D3") (pin "26") (pinfunction "SW10_26") (pintype "passive"))
      (node (ref "L10") (pin "2") (pinfunction "2_2") (pintype "passive"))
    )
    (net (code "22") (name "/PMIC_VDC") (class "Default")
      (node (ref "C122") (pin "1") (pinfunction "1_1") (pintype "passive"))
      (node (ref "D3") (pin "32") (pinfunction "VDC_32") (pintype "passive"))
      (node (ref "R22") (pin "2") (pinfunction "2_2") (pintype "passive"))
      (node (ref "R26") (pin "1") (pinfunction "1_1") (pintype "passive"))
    )
    (net (code "23") (name "/PWRON_L") (class "Default")
      (node (ref "R23") (pin "1") (pinfunction "1_1") (pintype "passive"))
    )
    (net (code "24") (name "/RESETn") (class "Default")
      (node (ref "C113") (pin "2") (pinfunction "2_2") (pintype "passive"))
      (node (ref "D3") (pin "40") (pinfunction "RESETB_40") (pintype "passive"))
    )
    (net (code "25") (name "/VDD_CPU_BIG_S0_FB") (class "Default")
      (node (ref "C65") (pin "1") (pinfunction "1_1") (pintype "passive"))
      (node (ref "D3") (pin "49") (pinfunction "VOUT1_49") (pintype "passive"))
      (node (ref "NT1") (pin "1") (pinfunction "1_1") (pintype "passive"))
      (node (ref "R11") (pin "2") (pinfunction "2_2") (pintype "passive"))
    )
    (net (code "26") (name "/VDD_CPU_LIT_S0_FB") (class "Default")
      (node (ref "C99") (pin "1") (pinfunction "1_1") (pintype "passive"))
      (node (ref "D3") (pin "56") (pinfunction "VOUT3_56") (pintype "passive"))
      (node (ref "NT4") (pin "1") (pinfunction "1_1") (pintype "passive"))
      (node (ref "R18") (pin "2") (pinfunction "2_2") (pintype "passive"))
    )
    (net (code "27") (name "/VDD_DDR_S0_FB") (class "Default")
      (node (ref "C121") (pin "1") (pinfunction "1_1") (pintype "passive"))
      (node (ref "D3") (pin "25") (pinfunction "VOUT10_25") (pintype "passive"))
      (node (ref "NT6") (pin "2") (pinfunction "2_2") (pintype "passive"))
      (node (ref "R25") (pin "2") (pinfunction "2_2") (pintype "passive"))
    )
    (net (code "28") (name "/VDD_GPU_S0_FB") (class "Default")
      (node (ref "C64") (pin "1") (pinfunction "1_1") (pintype "passive"))
      (node (ref "D3") (pin "46") (pinfunction "VOUT5_46") (pintype "passive"))
      (node (ref "NT2") (pin "2") (pinfunction "2_2") (pintype "passive"))
      (node (ref "R10") (pin "2") (pinfunction "2_2") (pintype "passive"))
    )
    (net (code "29") (name "/VDD_LOGIC_S0_FB") (class "Default")
      (node (ref "C117") (pin "1") (pinfunction "1_1") (pintype "passive"))
      (node (ref "D3") (pin "41") (pinfunction "VOUT7_41") (pintype "passive"))
      (node (ref "NT5") (pin "1") (pinfunction "1_1") (pintype "passive"))
      (node (ref "R24") (pin "2") (pinfunction "2_2") (pintype "passive"))
    )
    (net (code "30") (name "/VDD_NPU_S0_FB") (class "Default")
      (node (ref "C82") (pin "1") (pinfunction "1_1") (pintype "passive"))
      (node (ref "D3") (pin "37") (pinfunction "VOUT2_37") (pintype "passive"))
      (node (ref "NT3") (pin "1") (pinfunction "1_1") (pintype "passive"))
      (node (ref "R15") (pin "2") (pinfunction "2_2") (pintype "passive"))
    )
    (net (code "36") (name "GND") (class "Default")
      (node (ref "C100") (pin "2") (pinfunction "2_2") (pintype "passive"))
      (node (ref "C101") (pin "1") (pinfunction "1_1") (pintype "passive"))
      (node (ref "C102") (pin "2") (pinfunction "2_2") (pintype "passive"))
      (node (ref "C104") (pin "1") (pinfunction "1_1") (pintype "passive"))
      (node (ref "C106") (pin "2") (pinfunction "2_2") (pintype "passive"))
      (node (ref "C107") (pin "2") (pinfunction "2_2") (pintype "passive"))
      (node (ref "C108") (pin "2") (pinfunction "2_2") (pintype "passive"))
      (node (ref "C109") (pin "2") (pinfunction "2_2") (pintype "passive"))
      (node (ref "C111") (pin "1") (pinfunction "1_1") (pintype "passive"))
      (node (ref "C112") (pin "2") (pinfunction "2_2") (pintype "passive"))
      (node (ref "C113") (pin "1") (pinfunction "1_1") (pintype "passive"))
      (node (ref "C114") (pin "1") (pinfunction "1_1") (pintype "passive"))
      (node (ref "C115") (pin "1") (pinfunction "1_1") (pintype "passive"))
      (node (ref "C116") (pin "1") (pinfunction "1_1") (pintype "passive"))
      (node (ref "C119") (pin "2") (pinfunction "2_2") (pintype "passive"))
      (node (ref "C120") (pin "2") (pinfunction "2_2") (pintype "passive"))
      (node (ref "C122") (pin "2") (pinfunction "2_2") (pintype "passive"))
      (node (ref "C123") (pin "1") (pinfunction "1_1") (pintype "passive"))
      (node (ref "C57") (pin "2") (pinfunction "2_2") (pintype "passive"))
      (node (ref "C58") (pin "2") (pinfunction "2_2") (pintype "passive"))
      (node (ref "C59") (pin "2") (pinfunction "2_2") (pintype "passive"))
      (node (ref "C60") (pin "1") (pinfunction "1_1") (pintype "passive"))
      (node (ref "C61") (pin "1") (pinfunction "1_1") (pintype "passive"))
      (node (ref "C62") (pin "2") (pinfunction "2_2") (pintype "passive"))
      (node (ref "C63") (pin "2") (pinfunction "2_2") (pintype "passive"))
      (node (ref "C66") (pin "2") (pinfunction "2_2") (pintype "passive"))
      (node (ref "C67") (pin "2") (pinfunction "2_2") (pintype "passive"))
      (node (ref "C68") (pin "2") (pinfunction "2_2") (pintype "passive"))
      (node (ref "C69") (pin "1") (pinfunction "1_1") (pintype "passive"))
      (node (ref "C70") (pin "1") (pinfunction "1_1") (pintype "passive"))
      (node (ref "C71") (pin "2") (pinfunction "2_2") (pintype "passive"))
      (node (ref "C72") (pin "2") (pinfunction "2_2") (pintype "passive"))
      (node (ref "C73") (pin "1") (pinfunction "1_1") (pintype "passive"))
      (node (ref "C74") (pin "1") (pinfunction "1_1") (pintype "passive"))
      (node (ref "C76") (pin "2") (pinfunction "2_2") (pintype "passive"))
      (node (ref "C77") (pin "2") (pinfunction "2_2") (pintype "passive"))
      (node (ref "C79") (pin "2") (pinfunction "2_2") (pintype "passive"))
      (node (ref "C80") (pin "2") (pinfunction "2_2") (pintype "passive"))
      (node (ref "C81") (pin "2") (pinfunction "2_2") (pintype "passive"))
      (node (ref "C83") (pin "2") (pinfunction "2_2") (pintype "passive"))
      (node (ref "C84") (pin "1") (pinfunction "1_1") (pintype "passive"))
      (node (ref "C85") (pin "1") (pinfunction "1_1") (pintype "passive"))
      (node (ref "C86") (pin "1") (pinfunction "1_1") (pintype "passive"))
      (node (ref "C87") (pin "1") (pinfunction "1_1") (pintype "passive"))
      (node (ref "C88") (pin "2") (pinfunction "2_2") (pintype "passive"))
      (node (ref "C89") (pin "2") (pinfunction "2_2") (pintype "passive"))
      (node (ref "C90") (pin "1") (pinfunction "1_1") (pintype "passive"))
      (node (ref "C92") (pin "2") (pinfunction "2_2") (pintype "passive"))
      (node (ref "C93") (pin "2") (pinfunction "2_2") (pintype "passive"))
      (node (ref "C95") (pin "1") (pinfunction "1_1") (pintype "passive"))
      (node (ref "C96") (pin "2") (pinfunction "2_2") (pintype "passive"))
      (node (ref "C97") (pin "2") (pinfunction "2_2") (pintype "passive"))
      (node (ref "D3") (pin "69") (pinfunction "EPAD_69") (pintype "passive"))
      (node (ref "R13") (pin "2") (pinfunction "2_2") (pintype "passive"))
      (node (ref "R16") (pin "1") (pinfunction "1_1") (pintype "passive"))
      (node (ref "R19") (pin "1") (pinfunction "1_1") (pintype "passive"))
      (node (ref "R26") (pin "2") (pinfunction "2_2") (pintype "passive"))
      (node (ref "VD1") (pin "2") (pinfunction "A_2") (pintype "passive"))
      (node (ref "VD2") (pin "2") (pinfunction "A_2") (pintype "passive"))
    )
    (net (code "37") (name "Net-(D3B-PWRON)") (class "Default")
      (node (ref "C123") (pin "2") (pinfunction "2_2") (pintype "passive"))
      (node (ref "D3") (pin "4") (pinfunction "PWRON_4") (pintype "passive"))
      (node (ref "R23") (pin "2") (pinfunction "2_2") (pintype "passive"))
    )
    (net (code "38") (name "Net-(VD2-K)") (class "Default")
      (node (ref "C103") (pin "1") (pinfunction "1_1") (pintype "passive"))
      (node (ref "R22") (pin "1") (pinfunction "1_1") (pintype "passive"))
      (node (ref "VD2") (pin "1") (pinfunction "K_1") (pintype "passive"))
    )
    (net (code "39") (name "VCC5V0_SYS_S5") (class "Default")
      (node (ref "C101") (pin "2") (pinfunction "2_2") (pintype "passive"))
      (node (ref "C102") (pin "1") (pinfunction "1_1") (pintype "passive"))
      (node (ref "C103") (pin "2") (pinfunction "2_2") (pintype "passive"))
      (node (ref "C111") (pin "2") (pinfunction "2_2") (pintype "passive"))
      (node (ref "C112") (pin "1") (pinfunction "1_1") (pintype "passive"))
      (node (ref "C57") (pin "1") (pinfunction "1_1") (pintype "passive"))
      (node (ref "C58") (pin "1") (pinfunction "1_1") (pintype "passive"))
      (node (ref "C70") (pin "2") (pinfunction "2_2") (pintype "passive"))
      (node (ref "C71") (pin "1") (pinfunction "1_1") (pintype "passive"))
      (node (ref "C72") (pin "1") (pinfunction "1_1") (pintype "passive"))
      (node (ref "C87") (pin "2") (pinfunction "2_2") (pintype "passive"))
      (node (ref "C88") (pin "1") (pinfunction "1_1") (pintype "passive"))
      (node (ref "D3") (pin "1") (pinfunction "VCC9_1") (pintype "passive"))
      (node (ref "D3") (pin "22") (pinfunction "VCC4_22") (pintype "passive"))
      (node (ref "D3") (pin "27") (pinfunction "VCC10_27") (pintype "passive"))
      (node (ref "D3") (pin "28") (pinfunction "VCC6_28") (pintype "passive"))
      (node (ref "D3") (pin "33") (pinfunction "VCC2_33") (pintype "passive"))
      (node (ref "D3") (pin "34") (pinfunction "VCC2_34") (pintype "passive"))
      (node (ref "D3") (pin "43") (pinfunction "VCC7_43") (pintype "passive"))
      (node (ref "D3") (pin "44") (pinfunction "VCC5_44") (pintype "passive"))
      (node (ref "D3") (pin "52") (pinfunction "VCC1_52") (pintype "passive"))
      (node (ref "D3") (pin "53") (pinfunction "VCC1_53") (pintype "passive"))
      (node (ref "D3") (pin "54") (pinfunction "VCC3_54") (pintype "passive"))
      (node (ref "D3") (pin "64") (pinfunction "VCC12_64") (pintype "passive"))
      (node (ref "D3") (pin "7") (pinfunction "VCC8_7") (pintype "passive"))
      (node (ref "R20") (pin "2") (pinfunction "2_2") (pintype "passive"))
      (node (ref "R21") (pin "2") (pinfunction "2_2") (pintype "passive"))
      (node (ref "VD1") (pin "1") (pinfunction "K_1") (pintype "passive"))
    )
    (net (code "40") (name "VCCA") (class "Default")
      (node (ref "C104") (pin "2") (pinfunction "2_2") (pintype "passive"))
      (node (ref "D3") (pin "21") (pinfunction "VCCA_21") (pintype "passive"))
      (node (ref "R21") (pin "1") (pinfunction "1_1") (pintype "passive"))
    )
    (net (code "41") (name "VCCA1V8_PLDO2_S0") (class "Default")
      (node (ref "C61") (pin "2") (pinfunction "2_2") (pintype "passive"))
      (node (ref "D3") (pin "58") (pinfunction "PLDO2_58") (pintype "passive"))
    )
    (net (code "42") (name "VCCA1V8_PLDO6_S3") (class "Default")
      (node (ref "C100") (pin "1") (pinfunction "1_1") (pintype "passive"))
      (node (ref "D3") (pin "20") (pinfunction "VCCIO_20") (pintype "passive"))
      (node (ref "R232") (pin "1") (pinfunction "1_1") (pintype "passive"))
    )
    (net (code "43") (name "VCCA_1V8_S0") (class "Default")
      (node (ref "C60") (pin "2") (pinfunction "2_2") (pintype "passive"))
      (node (ref "D3") (pin "60") (pinfunction "PLDO1_60") (pintype "passive"))
      (node (ref "R232") (pin "2") (pinfunction "2_2") (pintype "passive"))
    )
    (net (code "44") (name "VCCA_3V3_S0") (class "Default")
      (node (ref "C73") (pin "2") (pinfunction "2_2") (pintype "passive"))
      (node (ref "D3") (pin "63") (pinfunction "PLDO4_63") (pintype "passive"))
    )
    (net (code "45") (name "VCCIO_SD_S0") (class "Default")
      (node (ref "C74") (pin "2") (pinfunction "2_2") (pintype "passive"))
      (node (ref "D3") (pin "65") (pinfunction "PLDO5_65") (pintype "passive"))
    )
    (net (code "46") (name "VCC_1V1_NLDO_S3") (class "Default")
      (node (ref "C83") (pin "1") (pinfunction "1_1") (pintype "passive"))
      (node (ref "C89") (pin "1") (pinfunction "1_1") (pintype "passive"))
      (node (ref "D3") (pin "13") (pinfunction "VCC13_13") (pintype "passive"))
      (node (ref "D3") (pin "9") (pinfunction "VCC14_9") (pintype "passive"))
    )
    (net (code "47") (name "VCC_1V8_S3") (class "Default")
      (node (ref "C106") (pin "1") (pinfunction "1_1") (pintype "passive"))
      (node (ref "C107") (pin "1") (pinfunction "1_1") (pintype "passive"))
      (node (ref "D3") (pin "5") (pinfunction "VOUT8_5") (pintype "passive"))
      (node (ref "L7") (pin "1") (pinfunction "1_1") (pintype "passive"))
    )
    (net (code "48") (name "VCC_2V0_PLDO_S3") (class "Default")
      (node (ref "C59") (pin "1") (pinfunction "1_1") (pintype "passive"))
      (node (ref "D3") (pin "59") (pinfunction "VCC11_59") (pintype "passive"))
    )
    (net (code "49") (name "VCC_3V3_S3") (class "Default")
      (node (ref "C108") (pin "1") (pinfunction "1_1") (pintype "passive"))
      (node (ref "C109") (pin "1") (pinfunction "1_1") (pintype "passive"))
      (node (ref "D3") (pin "24") (pinfunction "VOUT4_24") (pintype "passive"))
      (node (ref "L8") (pin "2") (pinfunction "2_2") (pintype "passive"))
    )
    (net (code "50") (name "VDD2_DDR_S3") (class "Default")
      (node (ref "C92") (pin "1") (pinfunction "1_1") (pintype "passive"))
      (node (ref "C93") (pin "1") (pinfunction "1_1") (pintype "passive"))
      (node (ref "C94") (pin "1") (pinfunction "1_1") (pintype "passive"))
      (node (ref "D3") (pin "67") (pinfunction "VOUT9_67") (pintype "passive"))
      (node (ref "L5") (pin "1") (pinfunction "1_1") (pintype "passive"))
      (node (ref "R17") (pin "1") (pinfunction "1_1") (pintype "passive"))
    )
    (net (code "51") (name "VDDA_0V75_S0") (class "Default")
      (node (ref "C95") (pin "2") (pinfunction "2_2") (pintype "passive"))
      (node (ref "D3") (pin "8") (pinfunction "NLDO5_8") (pintype "passive"))
    )
    (net (code "52") (name "VDDA_0V85_S0") (class "Default")
      (node (ref "C90") (pin "2") (pinfunction "2_2") (pintype "passive"))
      (node (ref "D3") (pin "10") (pinfunction "NLDO4_10") (pintype "passive"))
    )
    (net (code "53") (name "VDDA_1V2_S0") (class "Default")
      (node (ref "C69") (pin "2") (pinfunction "2_2") (pintype "passive"))
      (node (ref "D3") (pin "57") (pinfunction "PLDO3_57") (pintype "passive"))
    )
    (net (code "54") (name "VDDA_DDR_PLL_S0") (class "Default")
      (node (ref "C85") (pin "2") (pinfunction "2_2") (pintype "passive"))
      (node (ref "D3") (pin "12") (pinfunction "NLDO2_12") (pintype "passive"))
    )
    (net (code "55") (name "VDDA_HDMI_S0") (class "Default")
      (node (ref "C86") (pin "2") (pinfunction "2_2") (pintype "passive"))
      (node (ref "D3") (pin "11") (pinfunction "NLDO3_11") (pintype "passive"))
    )
    (net (code "56") (name "VDDQ_DDR_S0") (class "Default")
      (node (ref "C76") (pin "1") (pinfunction "1_1") (pintype "passive"))
      (node (ref "C77") (pin "1") (pinfunction "1_1") (pintype "passive"))
      (node (ref "C78") (pin "1") (pinfunction "1_1") (pintype "passive"))
      (node (ref "D3") (pin "30") (pinfunction "VOUT6_30") (pintype "passive"))
      (node (ref "L3") (pin "1") (pinfunction "1_1") (pintype "passive"))
      (node (ref "R14") (pin "1") (pinfunction "1_1") (pintype "passive"))
    )
    (net (code "57") (name "VDD_0V75_S3") (class "Default")
      (node (ref "C84") (pin "2") (pinfunction "2_2") (pintype "passive"))
      (node (ref "D3") (pin "14") (pinfunction "NLDO1_14") (pintype "passive"))
    )
    (net (code "58") (name "VDD_CPU_BIG_S0") (class "Default")
      (node (ref "C65") (pin "2") (pinfunction "2_2") (pintype "passive"))
      (node (ref "C66") (pin "1") (pinfunction "1_1") (pintype "passive"))
      (node (ref "C67") (pin "1") (pinfunction "1_1") (pintype "passive"))
      (node (ref "C68") (pin "1") (pinfunction "1_1") (pintype "passive"))
      (node (ref "L2") (pin "2") (pinfunction "2_2") (pintype "passive"))
      (node (ref "NT1") (pin "2") (pinfunction "2_2") (pintype "passive"))
      (node (ref "R11") (pin "1") (pinfunction "1_1") (pintype "passive"))
    )
    (net (code "59") (name "VDD_CPU_LIT_S0") (class "Default")
      (node (ref "C96") (pin "1") (pinfunction "1_1") (pintype "passive"))
      (node (ref "C97") (pin "1") (pinfunction "1_1") (pintype "passive"))
      (node (ref "C99") (pin "2") (pinfunction "2_2") (pintype "passive"))
      (node (ref "L6") (pin "2") (pinfunction "2_2") (pintype "passive"))
      (node (ref "NT4") (pin "2") (pinfunction "2_2") (pintype "passive"))
      (node (ref "R18") (pin "1") (pinfunction "1_1") (pintype "passive"))
    )
    (net (code "60") (name "VDD_DDR_S0") (class "Default")
      (node (ref "C119") (pin "1") (pinfunction "1_1") (pintype "passive"))
      (node (ref "C120") (pin "1") (pinfunction "1_1") (pintype "passive"))
      (node (ref "C121") (pin "2") (pinfunction "2_2") (pintype "passive"))
      (node (ref "L10") (pin "1") (pinfunction "1_1") (pintype "passive"))
      (node (ref "NT6") (pin "1") (pinfunction "1_1") (pintype "passive"))
      (node (ref "R25") (pin "1") (pinfunction "1_1") (pintype "passive"))
    )
    (net (code "61") (name "VDD_GPU_S0") (class "Default")
      (node (ref "C62") (pin "1") (pinfunction "1_1") (pintype "passive"))
      (node (ref "C63") (pin "1") (pinfunction "1_1") (pintype "passive"))
      (node (ref "C64") (pin "2") (pinfunction "2_2") (pintype "passive"))
      (node (ref "L1") (pin "1") (pinfunction "1_1") (pintype "passive"))
      (node (ref "NT2") (pin "1") (pinfunction "1_1") (pintype "passive"))
      (node (ref "R10") (pin "1") (pinfunction "1_1") (pintype "passive"))
      (node (ref "R12") (pin "1") (pinfunction "1_1") (pintype "passive"))
    )
    (net (code "62") (name "VDD_LOGIC_S0") (class "Default")
      (node (ref "C114") (pin "2") (pinfunction "2_2") (pintype "passive"))
      (node (ref "C115") (pin "2") (pinfunction "2_2") (pintype "passive"))
      (node (ref "C116") (pin "2") (pinfunction "2_2") (pintype "passive"))
      (node (ref "C117") (pin "2") (pinfunction "2_2") (pintype "passive"))
      (node (ref "L9") (pin "2") (pinfunction "2_2") (pintype "passive"))
      (node (ref "NT5") (pin "2") (pinfunction "2_2") (pintype "passive"))
      (node (ref "R24") (pin "1") (pinfunction "1_1") (pintype "passive"))
    )
    (net (code "63") (name "VDD_NPU_S0") (class "Default")
      (node (ref "C79") (pin "1") (pinfunction "1_1") (pintype "passive"))
      (node (ref "C80") (pin "1") (pinfunction "1_1") (pintype "passive"))
      (node (ref "C81") (pin "1") (pinfunction "1_1") (pintype "passive"))
      (node (ref "C82") (pin "2") (pinfunction "2_2") (pintype "passive"))
      (node (ref "L4") (pin "2") (pinfunction "2_2") (pintype "passive"))
      (node (ref "NT3") (pin "2") (pinfunction "2_2") (pintype "passive"))
      (node (ref "R15") (pin "1") (pinfunction "1_1") (pintype "passive"))
    )
    (net (code "64") (name "unconnected-(D3A-FB1-Pad48)") (class "Default")
      (node (ref "D3") (pin "48") (pinfunction "FB1_48") (pintype "passive+no_connect"))
    )
    (net (code "65") (name "unconnected-(D3A-FB2-Pad38)") (class "Default")
      (node (ref "D3") (pin "38") (pinfunction "FB2_38") (pintype "passive+no_connect"))
    )
    (net (code "66") (name "unconnected-(D3B-MISO-Pad16)") (class "Default")
      (node (ref "D3") (pin "16") (pinfunction "MISO_16") (pintype "passive+no_connect"))
    )
    (net (code "67") (name "unconnected-(D3B-SYNC-Pad2)") (class "Default")
      (node (ref "D3") (pin "2") (pinfunction "SYNC_2") (pintype "passive+no_connect"))
    )
    (net (code "68") (name "unconnected-(D3B-SYNC_CLK-Pad3)") (class "Default")
      (node (ref "D3") (pin "3") (pinfunction "SYNC_CLK_3") (pintype "passive+no_connect"))
    )
  )
)
